# Motor_Controller.net
KiCad netlist of a schematic drawn in EAGLE
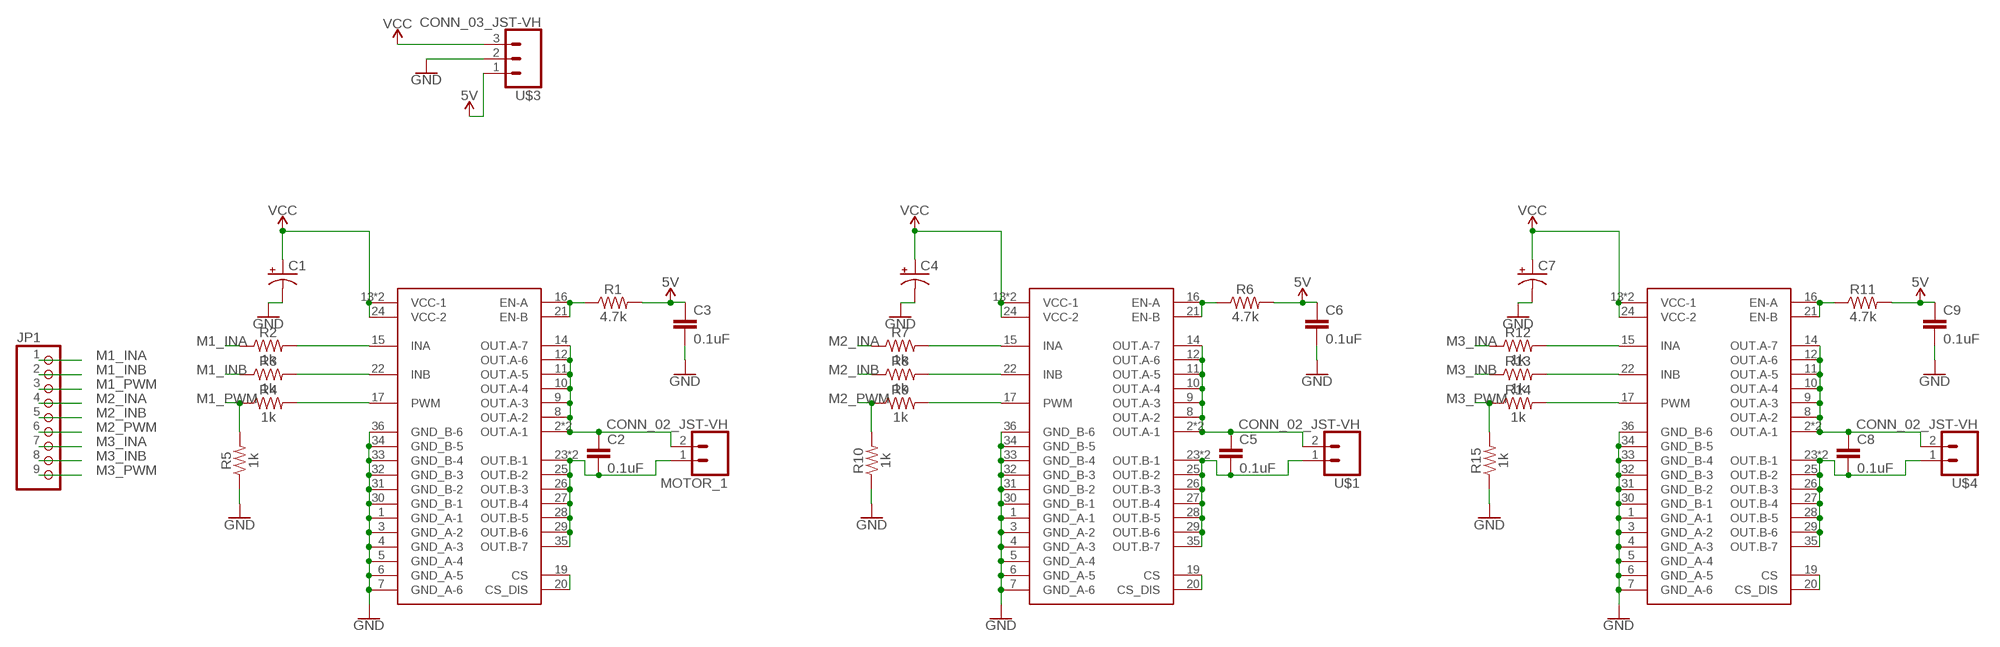
[diagram p0: schematic, sheet 1]

(export (version "E")
  (design (tool "Eeschema 10.0.6"))
  (components
    (comp (ref "C1")
      (value "CPOL-USE3.5-8")
      (footprint "eagle-import:E3,5-8")
      (libsource (lib "eagle-import") (part "CPOL-USE3.5-8"))
    )
    (comp (ref "C2")
      (value "0.1uF")
      (footprint "eagle-import:0603")
      (libsource (lib "eagle-import") (part "0.1UF-0603-25V-(+80/-20%)"))
    )
    (comp (ref "C3")
      (value "0.1uF")
      (footprint "eagle-import:0603")
      (libsource (lib "eagle-import") (part "0.1UF-0603-25V-(+80/-20%)"))
    )
    (comp (ref "C4")
      (value "CPOL-USE3.5-8")
      (footprint "eagle-import:E3,5-8")
      (libsource (lib "eagle-import") (part "CPOL-USE3.5-8"))
    )
    (comp (ref "C5")
      (value "0.1uF")
      (footprint "eagle-import:0603")
      (libsource (lib "eagle-import") (part "0.1UF-0603-25V-(+80/-20%)"))
    )
    (comp (ref "C6")
      (value "0.1uF")
      (footprint "eagle-import:0603")
      (libsource (lib "eagle-import") (part "0.1UF-0603-25V-(+80/-20%)"))
    )
    (comp (ref "C7")
      (value "CPOL-USE3.5-8")
      (footprint "eagle-import:E3,5-8")
      (libsource (lib "eagle-import") (part "CPOL-USE3.5-8"))
    )
    (comp (ref "C8")
      (value "0.1uF")
      (footprint "eagle-import:0603")
      (libsource (lib "eagle-import") (part "0.1UF-0603-25V-(+80/-20%)"))
    )
    (comp (ref "C9")
      (value "0.1uF")
      (footprint "eagle-import:0603")
      (libsource (lib "eagle-import") (part "0.1UF-0603-25V-(+80/-20%)"))
    )
    (comp (ref "JP1")
      (value "PINHD-1X9")
      (footprint "eagle-import:1X09")
      (libsource (lib "eagle-import") (part "PINHD-1X9"))
    )
    (comp (ref "M1")
      (value "M1")
      (footprint "eagle-import:SOP50P1030X247-36N")
      (fields (field (name "MANUFACTURER") "STMicroelectronics"))
      (libsource (lib "eagle-import") (part "SOP50P1030X247-36N"))
    )
    (comp (ref "M2")
      (value "M2")
      (footprint "eagle-import:SOP50P1030X247-36N")
      (fields (field (name "MANUFACTURER") "STMicroelectronics"))
      (libsource (lib "eagle-import") (part "SOP50P1030X247-36N"))
    )
    (comp (ref "M3")
      (value "M3")
      (footprint "eagle-import:SOP50P1030X247-36N")
      (fields (field (name "MANUFACTURER") "STMicroelectronics"))
      (libsource (lib "eagle-import") (part "SOP50P1030X247-36N"))
    )
    (comp (ref "MOTOR_1")
      (value "CONN_02_JST-VH")
      (footprint "eagle-import:B2P-VH")
      (libsource (lib "eagle-import") (part "CONN_02_JST-VH"))
    )
    (comp (ref "R1")
      (value "4.7k")
      (footprint "eagle-import:0603")
      (libsource (lib "eagle-import") (part "4.7KOHM-0603-1/10W-1%"))
    )
    (comp (ref "R2")
      (value "1k")
      (footprint "eagle-import:0603")
      (libsource (lib "eagle-import") (part "1KOHM-0603-1/10W-1%"))
    )
    (comp (ref "R3")
      (value "1k")
      (footprint "eagle-import:0603")
      (libsource (lib "eagle-import") (part "1KOHM-0603-1/10W-1%"))
    )
    (comp (ref "R4")
      (value "1k")
      (footprint "eagle-import:0603")
      (libsource (lib "eagle-import") (part "1KOHM-0603-1/10W-1%"))
    )
    (comp (ref "R5")
      (value "1k")
      (footprint "eagle-import:0603")
      (libsource (lib "eagle-import") (part "1KOHM-0603-1/10W-1%"))
    )
    (comp (ref "R6")
      (value "4.7k")
      (footprint "eagle-import:0603")
      (libsource (lib "eagle-import") (part "4.7KOHM-0603-1/10W-1%"))
    )
    (comp (ref "R7")
      (value "1k")
      (footprint "eagle-import:0603")
      (libsource (lib "eagle-import") (part "1KOHM-0603-1/10W-1%"))
    )
    (comp (ref "R8")
      (value "1k")
      (footprint "eagle-import:0603")
      (libsource (lib "eagle-import") (part "1KOHM-0603-1/10W-1%"))
    )
    (comp (ref "R9")
      (value "1k")
      (footprint "eagle-import:0603")
      (libsource (lib "eagle-import") (part "1KOHM-0603-1/10W-1%"))
    )
    (comp (ref "R10")
      (value "1k")
      (footprint "eagle-import:0603")
      (libsource (lib "eagle-import") (part "1KOHM-0603-1/10W-1%"))
    )
    (comp (ref "R11")
      (value "4.7k")
      (footprint "eagle-import:0603")
      (libsource (lib "eagle-import") (part "4.7KOHM-0603-1/10W-1%"))
    )
    (comp (ref "R12")
      (value "1k")
      (footprint "eagle-import:0603")
      (libsource (lib "eagle-import") (part "1KOHM-0603-1/10W-1%"))
    )
    (comp (ref "R13")
      (value "1k")
      (footprint "eagle-import:0603")
      (libsource (lib "eagle-import") (part "1KOHM-0603-1/10W-1%"))
    )
    (comp (ref "R14")
      (value "1k")
      (footprint "eagle-import:0603")
      (libsource (lib "eagle-import") (part "1KOHM-0603-1/10W-1%"))
    )
    (comp (ref "R15")
      (value "1k")
      (footprint "eagle-import:0603")
      (libsource (lib "eagle-import") (part "1KOHM-0603-1/10W-1%"))
    )
    (comp (ref "U$1")
      (value "CONN_02_JST-VH")
      (footprint "eagle-import:B2P-VH")
      (libsource (lib "eagle-import") (part "CONN_02_JST-VH"))
    )
    (comp (ref "U$3")
      (value "CONN_03_JST-VH")
      (footprint "eagle-import:B3P-VH")
      (libsource (lib "eagle-import") (part "CONN_03_JST-VH"))
    )
    (comp (ref "U$4")
      (value "CONN_02_JST-VH")
      (footprint "eagle-import:B2P-VH")
      (libsource (lib "eagle-import") (part "CONN_02_JST-VH"))
    )
  )
  (nets
    (net (code "1") (name "/M1_INA") (class "Default")
      (node (ref "JP1") (pin "1") (pinfunction "1_1") (pintype "passive"))
      (node (ref "R2") (pin "1") (pinfunction "1_1") (pintype "passive"))
    )
    (net (code "2") (name "/M1_INB") (class "Default")
      (node (ref "JP1") (pin "2") (pinfunction "2_2") (pintype "passive"))
      (node (ref "R3") (pin "1") (pinfunction "1_1") (pintype "passive"))
    )
    (net (code "3") (name "/M1_PWM") (class "Default")
      (node (ref "JP1") (pin "3") (pinfunction "3_3") (pintype "passive"))
      (node (ref "R4") (pin "1") (pinfunction "1_1") (pintype "passive"))
      (node (ref "R5") (pin "2") (pinfunction "2_2") (pintype "passive"))
    )
    (net (code "4") (name "/M2_INA") (class "Default")
      (node (ref "JP1") (pin "4") (pinfunction "4_4") (pintype "passive"))
      (node (ref "R7") (pin "1") (pinfunction "1_1") (pintype "passive"))
    )
    (net (code "5") (name "/M2_INB") (class "Default")
      (node (ref "JP1") (pin "5") (pinfunction "5_5") (pintype "passive"))
      (node (ref "R8") (pin "1") (pinfunction "1_1") (pintype "passive"))
    )
    (net (code "6") (name "/M2_PWM") (class "Default")
      (node (ref "JP1") (pin "6") (pinfunction "6_6") (pintype "passive"))
      (node (ref "R10") (pin "2") (pinfunction "2_2") (pintype "passive"))
      (node (ref "R9") (pin "1") (pinfunction "1_1") (pintype "passive"))
    )
    (net (code "7") (name "/M3_INA") (class "Default")
      (node (ref "JP1") (pin "7") (pinfunction "7_7") (pintype "passive"))
      (node (ref "R12") (pin "1") (pinfunction "1_1") (pintype "passive"))
    )
    (net (code "8") (name "/M3_INB") (class "Default")
      (node (ref "JP1") (pin "8") (pinfunction "8_8") (pintype "passive"))
      (node (ref "R13") (pin "1") (pinfunction "1_1") (pintype "passive"))
    )
    (net (code "9") (name "/M3_PWM") (class "Default")
      (node (ref "JP1") (pin "9") (pinfunction "9_9") (pintype "passive"))
      (node (ref "R14") (pin "1") (pinfunction "1_1") (pintype "passive"))
      (node (ref "R15") (pin "2") (pinfunction "2_2") (pintype "passive"))
    )
    (net (code "10") (name "5V") (class "Default")
      (node (ref "C3") (pin "1") (pinfunction "1_1") (pintype "passive"))
      (node (ref "C6") (pin "1") (pinfunction "1_1") (pintype "passive"))
      (node (ref "C9") (pin "1") (pinfunction "1_1") (pintype "passive"))
      (node (ref "R1") (pin "2") (pinfunction "2_2") (pintype "passive"))
      (node (ref "R11") (pin "2") (pinfunction "2_2") (pintype "passive"))
      (node (ref "R6") (pin "2") (pinfunction "2_2") (pintype "passive"))
      (node (ref "U$3") (pin "1") (pinfunction "1_1") (pintype "passive"))
    )
    (net (code "11") (name "GND") (class "Default")
      (node (ref "C1") (pin "-") (pinfunction "-_-") (pintype "passive"))
      (node (ref "C3") (pin "2") (pinfunction "2_2") (pintype "passive"))
      (node (ref "C4") (pin "-") (pinfunction "-_-") (pintype "passive"))
      (node (ref "C6") (pin "2") (pinfunction "2_2") (pintype "passive"))
      (node (ref "C7") (pin "-") (pinfunction "-_-") (pintype "passive"))
      (node (ref "C9") (pin "2") (pinfunction "2_2") (pintype "passive"))
      (node (ref "M1") (pin "1") (pinfunction "GND_A-1_1") (pintype "bidirectional"))
      (node (ref "M1") (pin "3") (pinfunction "GND_A-2_3") (pintype "bidirectional"))
      (node (ref "M1") (pin "30") (pinfunction "GND_B-1_30") (pintype "bidirectional"))
      (node (ref "M1") (pin "31") (pinfunction "GND_B-2_31") (pintype "bidirectional"))
      (node (ref "M1") (pin "32") (pinfunction "GND_B-3_32") (pintype "bidirectional"))
      (node (ref "M1") (pin "33") (pinfunction "GND_B-4_33") (pintype "bidirectional"))
      (node (ref "M1") (pin "34") (pinfunction "GND_B-5_34") (pintype "bidirectional"))
      (node (ref "M1") (pin "36") (pinfunction "GND_B-6_36") (pintype "bidirectional"))
      (node (ref "M1") (pin "4") (pinfunction "GND_A-3_4") (pintype "bidirectional"))
      (node (ref "M1") (pin "5") (pinfunction "GND_A-4_5") (pintype "bidirectional"))
      (node (ref "M1") (pin "6") (pinfunction "GND_A-5_6") (pintype "bidirectional"))
      (node (ref "M1") (pin "7") (pinfunction "GND_A-6_7") (pintype "bidirectional"))
      (node (ref "M2") (pin "1") (pinfunction "GND_A-1_1") (pintype "bidirectional"))
      (node (ref "M2") (pin "3") (pinfunction "GND_A-2_3") (pintype "bidirectional"))
      (node (ref "M2") (pin "30") (pinfunction "GND_B-1_30") (pintype "bidirectional"))
      (node (ref "M2") (pin "31") (pinfunction "GND_B-2_31") (pintype "bidirectional"))
      (node (ref "M2") (pin "32") (pinfunction "GND_B-3_32") (pintype "bidirectional"))
      (node (ref "M2") (pin "33") (pinfunction "GND_B-4_33") (pintype "bidirectional"))
      (node (ref "M2") (pin "34") (pinfunction "GND_B-5_34") (pintype "bidirectional"))
      (node (ref "M2") (pin "36") (pinfunction "GND_B-6_36") (pintype "bidirectional"))
      (node (ref "M2") (pin "4") (pinfunction "GND_A-3_4") (pintype "bidirectional"))
      (node (ref "M2") (pin "5") (pinfunction "GND_A-4_5") (pintype "bidirectional"))
      (node (ref "M2") (pin "6") (pinfunction "GND_A-5_6") (pintype "bidirectional"))
      (node (ref "M2") (pin "7") (pinfunction "GND_A-6_7") (pintype "bidirectional"))
      (node (ref "M3") (pin "1") (pinfunction "GND_A-1_1") (pintype "bidirectional"))
      (node (ref "M3") (pin "3") (pinfunction "GND_A-2_3") (pintype "bidirectional"))
      (node (ref "M3") (pin "30") (pinfunction "GND_B-1_30") (pintype "bidirectional"))
      (node (ref "M3") (pin "31") (pinfunction "GND_B-2_31") (pintype "bidirectional"))
      (node (ref "M3") (pin "32") (pinfunction "GND_B-3_32") (pintype "bidirectional"))
      (node (ref "M3") (pin "33") (pinfunction "GND_B-4_33") (pintype "bidirectional"))
      (node (ref "M3") (pin "34") (pinfunction "GND_B-5_34") (pintype "bidirectional"))
      (node (ref "M3") (pin "36") (pinfunction "GND_B-6_36") (pintype "bidirectional"))
      (node (ref "M3") (pin "4") (pinfunction "GND_A-3_4") (pintype "bidirectional"))
      (node (ref "M3") (pin "5") (pinfunction "GND_A-4_5") (pintype "bidirectional"))
      (node (ref "M3") (pin "6") (pinfunction "GND_A-5_6") (pintype "bidirectional"))
      (node (ref "M3") (pin "7") (pinfunction "GND_A-6_7") (pintype "bidirectional"))
      (node (ref "R10") (pin "1") (pinfunction "1_1") (pintype "passive"))
      (node (ref "R15") (pin "1") (pinfunction "1_1") (pintype "passive"))
      (node (ref "R5") (pin "1") (pinfunction "1_1") (pintype "passive"))
      (node (ref "U$3") (pin "2") (pinfunction "2_2") (pintype "passive"))
    )
    (net (code "12") (name "Net-(M1-CS)") (class "Default")
      (node (ref "M1") (pin "19") (pinfunction "CS_19") (pintype "bidirectional"))
      (node (ref "M1") (pin "20") (pinfunction "CS_DIS_20") (pintype "bidirectional"))
    )
    (net (code "13") (name "Net-(M1-EN-A)") (class "Default")
      (node (ref "M1") (pin "16") (pinfunction "EN-A_16") (pintype "bidirectional"))
      (node (ref "M1") (pin "21") (pinfunction "EN-B_21") (pintype "bidirectional"))
      (node (ref "R1") (pin "1") (pinfunction "1_1") (pintype "passive"))
    )
    (net (code "14") (name "Net-(M1-INA)") (class "Default")
      (node (ref "M1") (pin "15") (pinfunction "INA_15") (pintype "bidirectional"))
      (node (ref "R2") (pin "2") (pinfunction "2_2") (pintype "passive"))
    )
    (net (code "15") (name "Net-(M1-INB)") (class "Default")
      (node (ref "M1") (pin "22") (pinfunction "INB_22") (pintype "bidirectional"))
      (node (ref "R3") (pin "2") (pinfunction "2_2") (pintype "passive"))
    )
    (net (code "16") (name "Net-(M1-OUT.A-2)") (class "Default")
      (node (ref "C2") (pin "1") (pinfunction "1_1") (pintype "passive"))
      (node (ref "M1") (pin "10") (pinfunction "OUT.A-4_10") (pintype "bidirectional"))
      (node (ref "M1") (pin "11") (pinfunction "OUT.A-5_11") (pintype "bidirectional"))
      (node (ref "M1") (pin "12") (pinfunction "OUT.A-6_12") (pintype "bidirectional"))
      (node (ref "M1") (pin "14") (pinfunction "OUT.A-7_14") (pintype "bidirectional"))
      (node (ref "M1") (pin "2") (pinfunction "OUT.A-1_2") (pintype "bidirectional"))
      (node (ref "M1") (pin "8") (pinfunction "OUT.A-2_8") (pintype "bidirectional"))
      (node (ref "M1") (pin "9") (pinfunction "OUT.A-3_9") (pintype "bidirectional"))
      (node (ref "M1") (pin "SLUG2") (pinfunction "OUT.A-1_SLUG2") (pintype "bidirectional"))
      (node (ref "MOTOR_1") (pin "2") (pinfunction "2_2") (pintype "passive"))
    )
    (net (code "17") (name "Net-(M1-OUT.B-2)") (class "Default")
      (node (ref "C2") (pin "2") (pinfunction "2_2") (pintype "passive"))
      (node (ref "M1") (pin "23") (pinfunction "OUT.B-1_23") (pintype "bidirectional"))
      (node (ref "M1") (pin "25") (pinfunction "OUT.B-2_25") (pintype "bidirectional"))
      (node (ref "M1") (pin "26") (pinfunction "OUT.B-3_26") (pintype "bidirectional"))
      (node (ref "M1") (pin "27") (pinfunction "OUT.B-4_27") (pintype "bidirectional"))
      (node (ref "M1") (pin "28") (pinfunction "OUT.B-5_28") (pintype "bidirectional"))
      (node (ref "M1") (pin "29") (pinfunction "OUT.B-6_29") (pintype "bidirectional"))
      (node (ref "M1") (pin "35") (pinfunction "OUT.B-7_35") (pintype "bidirectional"))
      (node (ref "M1") (pin "SLUG3") (pinfunction "OUT.B-1_SLUG3") (pintype "bidirectional"))
      (node (ref "MOTOR_1") (pin "1") (pinfunction "1_1") (pintype "passive"))
    )
    (net (code "18") (name "Net-(M1-PWM)") (class "Default")
      (node (ref "M1") (pin "17") (pinfunction "PWM_17") (pintype "bidirectional"))
      (node (ref "R4") (pin "2") (pinfunction "2_2") (pintype "passive"))
    )
    (net (code "19") (name "Net-(M2-CS)") (class "Default")
      (node (ref "M2") (pin "19") (pinfunction "CS_19") (pintype "bidirectional"))
      (node (ref "M2") (pin "20") (pinfunction "CS_DIS_20") (pintype "bidirectional"))
    )
    (net (code "20") (name "Net-(M2-EN-A)") (class "Default")
      (node (ref "M2") (pin "16") (pinfunction "EN-A_16") (pintype "bidirectional"))
      (node (ref "M2") (pin "21") (pinfunction "EN-B_21") (pintype "bidirectional"))
      (node (ref "R6") (pin "1") (pinfunction "1_1") (pintype "passive"))
    )
    (net (code "21") (name "Net-(M2-INA)") (class "Default")
      (node (ref "M2") (pin "15") (pinfunction "INA_15") (pintype "bidirectional"))
      (node (ref "R7") (pin "2") (pinfunction "2_2") (pintype "passive"))
    )
    (net (code "22") (name "Net-(M2-INB)") (class "Default")
      (node (ref "M2") (pin "22") (pinfunction "INB_22") (pintype "bidirectional"))
      (node (ref "R8") (pin "2") (pinfunction "2_2") (pintype "passive"))
    )
    (net (code "23") (name "Net-(M2-OUT.A-2)") (class "Default")
      (node (ref "C5") (pin "1") (pinfunction "1_1") (pintype "passive"))
      (node (ref "M2") (pin "10") (pinfunction "OUT.A-4_10") (pintype "bidirectional"))
      (node (ref "M2") (pin "11") (pinfunction "OUT.A-5_11") (pintype "bidirectional"))
      (node (ref "M2") (pin "12") (pinfunction "OUT.A-6_12") (pintype "bidirectional"))
      (node (ref "M2") (pin "14") (pinfunction "OUT.A-7_14") (pintype "bidirectional"))
      (node (ref "M2") (pin "2") (pinfunction "OUT.A-1_2") (pintype "bidirectional"))
      (node (ref "M2") (pin "8") (pinfunction "OUT.A-2_8") (pintype "bidirectional"))
      (node (ref "M2") (pin "9") (pinfunction "OUT.A-3_9") (pintype "bidirectional"))
      (node (ref "M2") (pin "SLUG2") (pinfunction "OUT.A-1_SLUG2") (pintype "bidirectional"))
      (node (ref "U$1") (pin "2") (pinfunction "2_2") (pintype "passive"))
    )
    (net (code "24") (name "Net-(M2-OUT.B-2)") (class "Default")
      (node (ref "C5") (pin "2") (pinfunction "2_2") (pintype "passive"))
      (node (ref "M2") (pin "23") (pinfunction "OUT.B-1_23") (pintype "bidirectional"))
      (node (ref "M2") (pin "25") (pinfunction "OUT.B-2_25") (pintype "bidirectional"))
      (node (ref "M2") (pin "26") (pinfunction "OUT.B-3_26") (pintype "bidirectional"))
      (node (ref "M2") (pin "27") (pinfunction "OUT.B-4_27") (pintype "bidirectional"))
      (node (ref "M2") (pin "28") (pinfunction "OUT.B-5_28") (pintype "bidirectional"))
      (node (ref "M2") (pin "29") (pinfunction "OUT.B-6_29") (pintype "bidirectional"))
      (node (ref "M2") (pin "35") (pinfunction "OUT.B-7_35") (pintype "bidirectional"))
      (node (ref "M2") (pin "SLUG3") (pinfunction "OUT.B-1_SLUG3") (pintype "bidirectional"))
      (node (ref "U$1") (pin "1") (pinfunction "1_1") (pintype "passive"))
    )
    (net (code "25") (name "Net-(M2-PWM)") (class "Default")
      (node (ref "M2") (pin "17") (pinfunction "PWM_17") (pintype "bidirectional"))
      (node (ref "R9") (pin "2") (pinfunction "2_2") (pintype "passive"))
    )
    (net (code "26") (name "Net-(M3-CS)") (class "Default")
      (node (ref "M3") (pin "19") (pinfunction "CS_19") (pintype "bidirectional"))
      (node (ref "M3") (pin "20") (pinfunction "CS_DIS_20") (pintype "bidirectional"))
    )
    (net (code "27") (name "Net-(M3-EN-A)") (class "Default")
      (node (ref "M3") (pin "16") (pinfunction "EN-A_16") (pintype "bidirectional"))
      (node (ref "M3") (pin "21") (pinfunction "EN-B_21") (pintype "bidirectional"))
      (node (ref "R11") (pin "1") (pinfunction "1_1") (pintype "passive"))
    )
    (net (code "28") (name "Net-(M3-INA)") (class "Default")
      (node (ref "M3") (pin "15") (pinfunction "INA_15") (pintype "bidirectional"))
      (node (ref "R12") (pin "2") (pinfunction "2_2") (pintype "passive"))
    )
    (net (code "29") (name "Net-(M3-INB)") (class "Default")
      (node (ref "M3") (pin "22") (pinfunction "INB_22") (pintype "bidirectional"))
      (node (ref "R13") (pin "2") (pinfunction "2_2") (pintype "passive"))
    )
    (net (code "30") (name "Net-(M3-OUT.A-2)") (class "Default")
      (node (ref "C8") (pin "1") (pinfunction "1_1") (pintype "passive"))
      (node (ref "M3") (pin "10") (pinfunction "OUT.A-4_10") (pintype "bidirectional"))
      (node (ref "M3") (pin "11") (pinfunction "OUT.A-5_11") (pintype "bidirectional"))
      (node (ref "M3") (pin "12") (pinfunction "OUT.A-6_12") (pintype "bidirectional"))
      (node (ref "M3") (pin "14") (pinfunction "OUT.A-7_14") (pintype "bidirectional"))
      (node (ref "M3") (pin "2") (pinfunction "OUT.A-1_2") (pintype "bidirectional"))
      (node (ref "M3") (pin "8") (pinfunction "OUT.A-2_8") (pintype "bidirectional"))
      (node (ref "M3") (pin "9") (pinfunction "OUT.A-3_9") (pintype "bidirectional"))
      (node (ref "M3") (pin "SLUG2") (pinfunction "OUT.A-1_SLUG2") (pintype "bidirectional"))
      (node (ref "U$4") (pin "2") (pinfunction "2_2") (pintype "passive"))
    )
    (net (code "31") (name "Net-(M3-OUT.B-2)") (class "Default")
      (node (ref "C8") (pin "2") (pinfunction "2_2") (pintype "passive"))
      (node (ref "M3") (pin "23") (pinfunction "OUT.B-1_23") (pintype "bidirectional"))
      (node (ref "M3") (pin "25") (pinfunction "OUT.B-2_25") (pintype "bidirectional"))
      (node (ref "M3") (pin "26") (pinfunction "OUT.B-3_26") (pintype "bidirectional"))
      (node (ref "M3") (pin "27") (pinfunction "OUT.B-4_27") (pintype "bidirectional"))
      (node (ref "M3") (pin "28") (pinfunction "OUT.B-5_28") (pintype "bidirectional"))
      (node (ref "M3") (pin "29") (pinfunction "OUT.B-6_29") (pintype "bidirectional"))
      (node (ref "M3") (pin "35") (pinfunction "OUT.B-7_35") (pintype "bidirectional"))
      (node (ref "M3") (pin "SLUG3") (pinfunction "OUT.B-1_SLUG3") (pintype "bidirectional"))
      (node (ref "U$4") (pin "1") (pinfunction "1_1") (pintype "passive"))
    )
    (net (code "32") (name "Net-(M3-PWM)") (class "Default")
      (node (ref "M3") (pin "17") (pinfunction "PWM_17") (pintype "bidirectional"))
      (node (ref "R14") (pin "2") (pinfunction "2_2") (pintype "passive"))
    )
    (net (code "33") (name "VCC") (class "Default")
      (node (ref "C1") (pin "+") (pinfunction "+_+") (pintype "passive"))
      (node (ref "C4") (pin "+") (pinfunction "+_+") (pintype "passive"))
      (node (ref "C7") (pin "+") (pinfunction "+_+") (pintype "passive"))
      (node (ref "M1") (pin "13") (pinfunction "VCC-1_13") (pintype "bidirectional"))
      (node (ref "M1") (pin "24") (pinfunction "VCC-2_24") (pintype "bidirectional"))
      (node (ref "M1") (pin "SLUG1") (pinfunction "VCC-1_SLUG1") (pintype "bidirectional"))
      (node (ref "M2") (pin "13") (pinfunction "VCC-1_13") (pintype "bidirectional"))
      (node (ref "M2") (pin "24") (pinfunction "VCC-2_24") (pintype "bidirectional"))
      (node (ref "M2") (pin "SLUG1") (pinfunction "VCC-1_SLUG1") (pintype "bidirectional"))
      (node (ref "M3") (pin "13") (pinfunction "VCC-1_13") (pintype "bidirectional"))
      (node (ref "M3") (pin "24") (pinfunction "VCC-2_24") (pintype "bidirectional"))
      (node (ref "M3") (pin "SLUG1") (pinfunction "VCC-1_SLUG1") (pintype "bidirectional"))
      (node (ref "U$3") (pin "3") (pinfunction "3_3") (pintype "passive"))
    )
  )
)
